# Grove_-_Sunlight_Sensor_v1_0.net
KiCad netlist of a schematic drawn in EAGLE
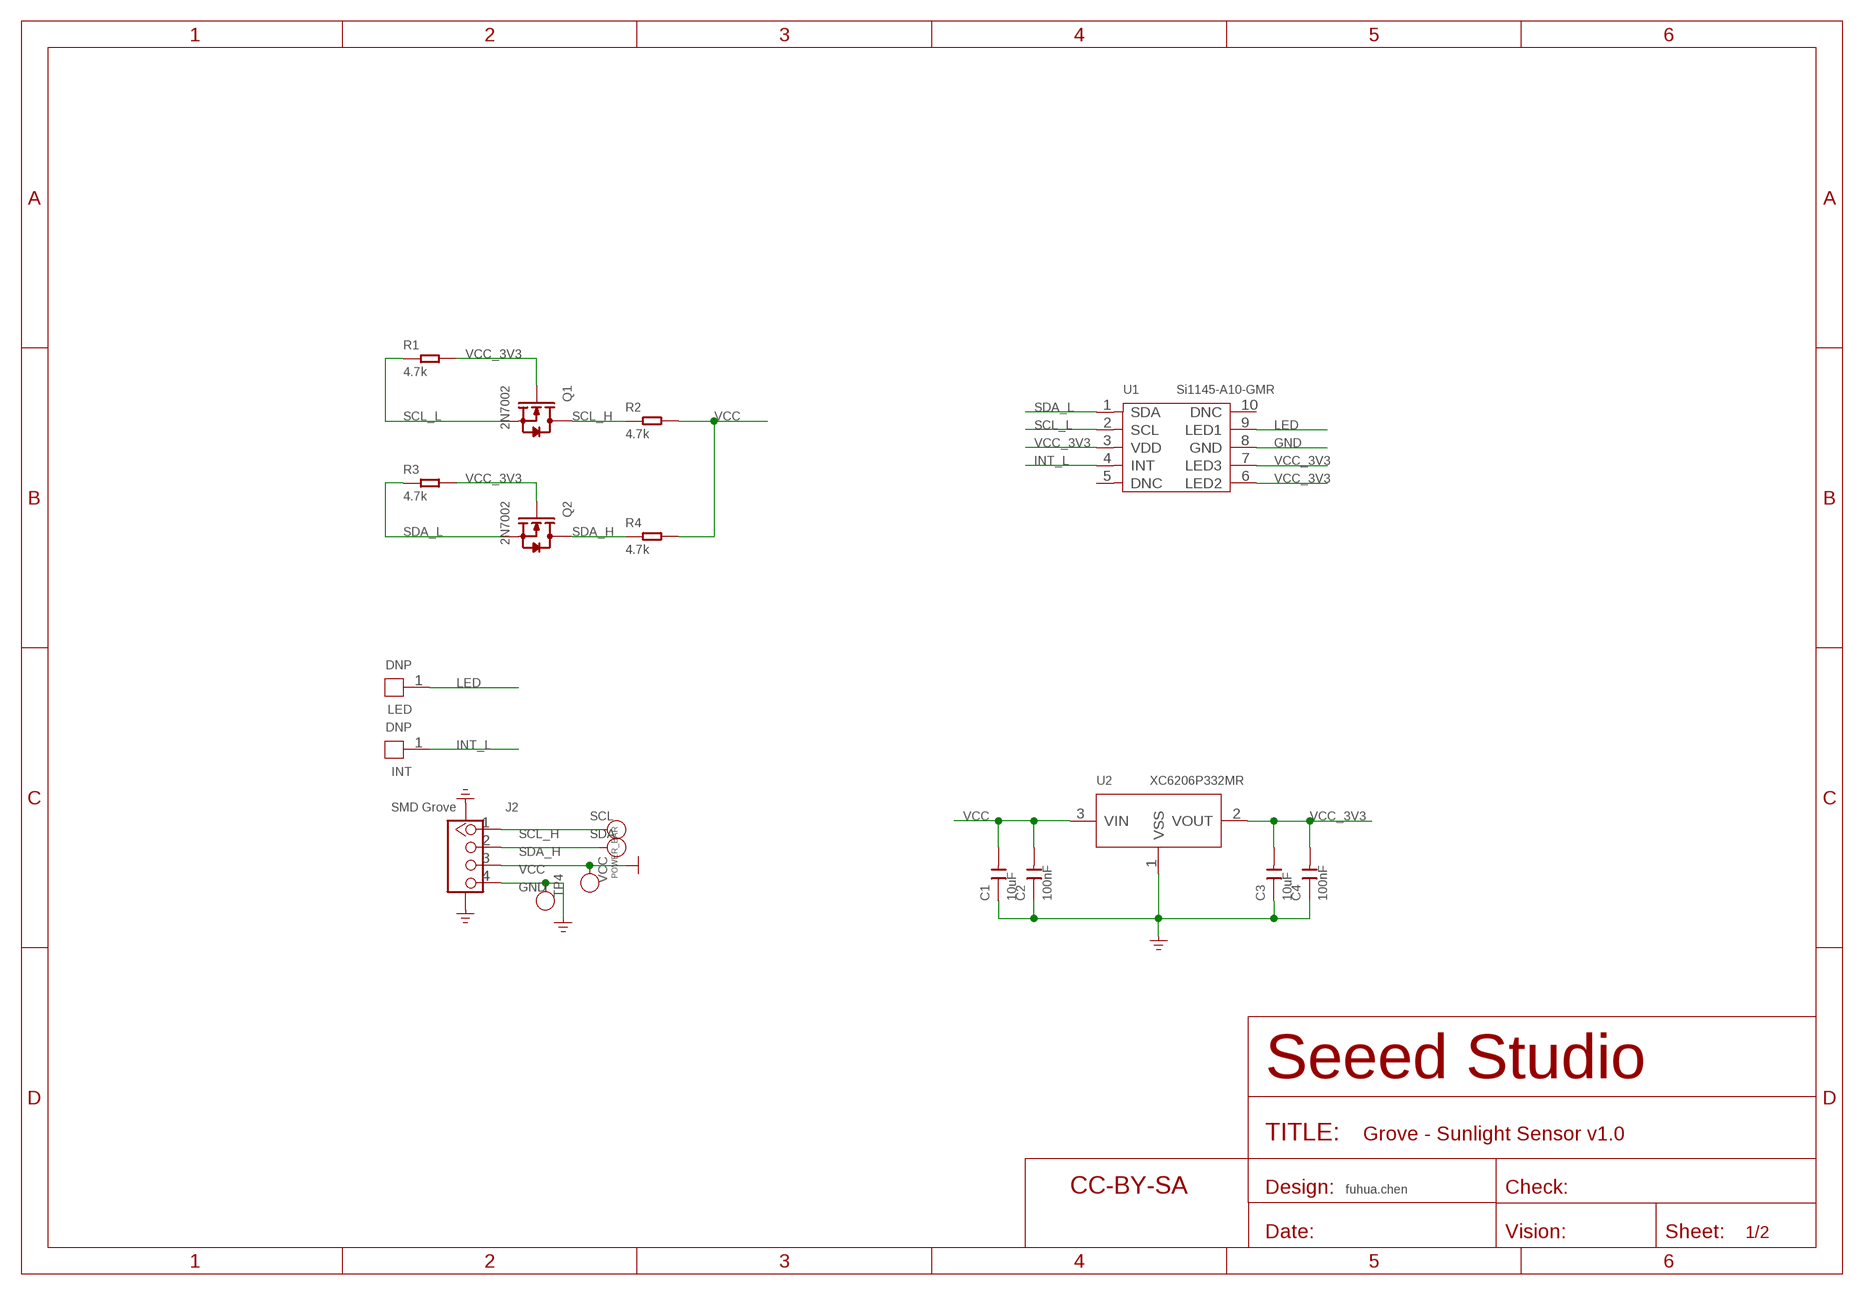
[diagram p0: schematic, sheet 1]
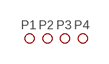
[diagram p1: schematic, sheet 2]

(export (version "E")
  (design (tool "Eeschema 10.0.6"))
  (components
    (comp (ref "C1")
      (value "10uF")
      (footprint "eagle-import:C0603")
      (libsource (lib "eagle-import") (part "CAP-0603"))
    )
    (comp (ref "C2")
      (value "100nF")
      (footprint "eagle-import:C0603")
      (libsource (lib "eagle-import") (part "CAP-0603"))
    )
    (comp (ref "C3")
      (value "10uF")
      (footprint "eagle-import:C0603")
      (libsource (lib "eagle-import") (part "CAP-0603"))
    )
    (comp (ref "C4")
      (value "100nF")
      (footprint "eagle-import:C0603")
      (libsource (lib "eagle-import") (part "CAP-0603"))
    )
    (comp (ref "FR")
      (value "SEEEDSTUDIO-OPEN-SCH-FRAME")
      (footprint "eagle-import:SEEEDSTUDIO-PCB-FRAME")
      (libsource (lib "eagle-import") (part "SEEEDSTUDIO-OPEN-SCH-FRAME"))
    )
    (comp (ref "INT")
      (value "DNP")
      (footprint "eagle-import:1P-80_40MIL")
      (libsource (lib "eagle-import") (part "HEADER-1P-40"))
    )
    (comp (ref "J2")
      (value "SMD Grove")
      (footprint "eagle-import:HW4-SMD-2.0")
      (libsource (lib "eagle-import") (part "GROVE-CONNECTOR-SMD'DD'"))
    )
    (comp (ref "LED")
      (value "DNP")
      (footprint "eagle-import:1P-80_40MIL")
      (libsource (lib "eagle-import") (part "HEADER-1P-40"))
    )
    (comp (ref "Q1")
      (value "2N7002")
      (footprint "eagle-import:SOT-23")
      (libsource (lib "eagle-import") (part "MOSFET-N'SOT23'"))
    )
    (comp (ref "Q2")
      (value "2N7002")
      (footprint "eagle-import:SOT-23")
      (libsource (lib "eagle-import") (part "MOSFET-N'SOT23'"))
    )
    (comp (ref "R1")
      (value "4.7k")
      (footprint "eagle-import:R0603")
      (libsource (lib "eagle-import") (part "RES-0603"))
    )
    (comp (ref "R2")
      (value "4.7k")
      (footprint "eagle-import:R0603")
      (libsource (lib "eagle-import") (part "RES-0603"))
    )
    (comp (ref "R3")
      (value "4.7k")
      (footprint "eagle-import:R0603")
      (libsource (lib "eagle-import") (part "RES-0603"))
    )
    (comp (ref "R4")
      (value "4.7k")
      (footprint "eagle-import:R0603")
      (libsource (lib "eagle-import") (part "RES-0603"))
    )
    (comp (ref "SCL")
      (value "TEST-POINT'4545'")
      (footprint "eagle-import:TP-D45MIL")
      (fields (field (name "PARTNO") "DNP"))
      (libsource (lib "eagle-import") (part "TEST-POINT'4545'"))
    )
    (comp (ref "SDA")
      (value "TEST-POINT'4545'")
      (footprint "eagle-import:TP-D45MIL")
      (fields (field (name "PARTNO") "DNP"))
      (libsource (lib "eagle-import") (part "TEST-POINT'4545'"))
    )
    (comp (ref "TP4")
      (value "TEST-POINT'4545'")
      (footprint "eagle-import:TP-D45MIL")
      (fields (field (name "PARTNO") "DNP"))
      (libsource (lib "eagle-import") (part "TEST-POINT'4545'"))
    )
    (comp (ref "U1")
      (value "Si1145-A10-GMR")
      (footprint "eagle-import:DFN10-0.5-2X2MM")
      (libsource (lib "eagle-import") (part "SENSOR-OPTICAL-SI1145/46/47"))
    )
    (comp (ref "U2")
      (value "XC6206P332MR")
      (footprint "eagle-import:SOT-23")
      (libsource (lib "eagle-import") (part "PMIC-XC6206PMR"))
    )
    (comp (ref "VCC")
      (value "TEST-POINT'4545'")
      (footprint "eagle-import:TP-D45MIL")
      (fields (field (name "PARTNO") "DNP"))
      (libsource (lib "eagle-import") (part "TEST-POINT'4545'"))
    )
    (comp (ref "P1")
      (value "PAD-MARK'ANNULAR'")
      (footprint "eagle-import:ROUND-MARK-1.0")
      (fields (field (name "PARTNO") "DNP"))
      (libsource (lib "eagle-import") (part "PAD-MARK'ANNULAR'"))
    )
    (comp (ref "P2")
      (value "PAD-MARK'ANNULAR'")
      (footprint "eagle-import:ROUND-MARK-1.0")
      (fields (field (name "PARTNO") "DNP"))
      (libsource (lib "eagle-import") (part "PAD-MARK'ANNULAR'"))
    )
    (comp (ref "P3")
      (value "PAD-MARK'ANNULAR'")
      (footprint "eagle-import:ROUND-MARK-1.0")
      (fields (field (name "PARTNO") "DNP"))
      (libsource (lib "eagle-import") (part "PAD-MARK'ANNULAR'"))
    )
    (comp (ref "P4")
      (value "PAD-MARK'ANNULAR'")
      (footprint "eagle-import:ROUND-MARK-1.0")
      (fields (field (name "PARTNO") "DNP"))
      (libsource (lib "eagle-import") (part "PAD-MARK'ANNULAR'"))
    )
  )
  (nets
    (net (code "1") (name "GND") (class "Default")
      (node (ref "C1") (pin "1") (pinfunction "1_1") (pintype "passive"))
      (node (ref "C2") (pin "1") (pinfunction "1_1") (pintype "passive"))
      (node (ref "C3") (pin "1") (pinfunction "1_1") (pintype "passive"))
      (node (ref "C4") (pin "1") (pinfunction "1_1") (pintype "passive"))
      (node (ref "J2") (pin "4") (pinfunction "4_4") (pintype "bidirectional"))
      (node (ref "J2") (pin "SS1") (pinfunction "SS1_SS1") (pintype "bidirectional"))
      (node (ref "J2") (pin "SS2") (pinfunction "SS2_SS2") (pintype "bidirectional"))
      (node (ref "TP4") (pin "T") (pinfunction "T_T") (pintype "bidirectional"))
      (node (ref "U1") (pin "8") (pinfunction "GND_8") (pintype "bidirectional"))
      (node (ref "U2") (pin "1") (pinfunction "VSS_1") (pintype "bidirectional"))
    )
    (net (code "2") (name "INT_L") (class "Default")
      (node (ref "INT") (pin "1") (pinfunction "1_1") (pintype "bidirectional"))
      (node (ref "U1") (pin "4") (pinfunction "INT_4") (pintype "bidirectional"))
    )
    (net (code "3") (name "LED") (class "Default")
      (node (ref "LED") (pin "1") (pinfunction "1_1") (pintype "bidirectional"))
      (node (ref "U1") (pin "9") (pinfunction "LED1_9") (pintype "bidirectional"))
    )
    (net (code "4") (name "SCL_H") (class "Default")
      (node (ref "J2") (pin "1") (pinfunction "1_1") (pintype "bidirectional"))
      (node (ref "Q1") (pin "3") (pinfunction "D_3") (pintype "passive"))
      (node (ref "R2") (pin "1") (pinfunction "1_1") (pintype "passive"))
      (node (ref "SCL") (pin "T") (pinfunction "T_T") (pintype "bidirectional"))
    )
    (net (code "5") (name "SCL_L") (class "Default")
      (node (ref "Q1") (pin "2") (pinfunction "S_2") (pintype "passive"))
      (node (ref "R1") (pin "1") (pinfunction "1_1") (pintype "passive"))
      (node (ref "U1") (pin "2") (pinfunction "SCL_2") (pintype "bidirectional"))
    )
    (net (code "6") (name "SDA_H") (class "Default")
      (node (ref "J2") (pin "2") (pinfunction "2_2") (pintype "bidirectional"))
      (node (ref "Q2") (pin "3") (pinfunction "D_3") (pintype "passive"))
      (node (ref "R4") (pin "1") (pinfunction "1_1") (pintype "passive"))
      (node (ref "SDA") (pin "T") (pinfunction "T_T") (pintype "bidirectional"))
    )
    (net (code "7") (name "SDA_L") (class "Default")
      (node (ref "Q2") (pin "2") (pinfunction "S_2") (pintype "passive"))
      (node (ref "R3") (pin "1") (pinfunction "1_1") (pintype "passive"))
      (node (ref "U1") (pin "1") (pinfunction "SDA_1") (pintype "bidirectional"))
    )
    (net (code "8") (name "VCC") (class "Default")
      (node (ref "C1") (pin "2") (pinfunction "2_2") (pintype "passive"))
      (node (ref "C2") (pin "2") (pinfunction "2_2") (pintype "passive"))
      (node (ref "J2") (pin "3") (pinfunction "3_3") (pintype "bidirectional"))
      (node (ref "R2") (pin "2") (pinfunction "2_2") (pintype "passive"))
      (node (ref "R4") (pin "2") (pinfunction "2_2") (pintype "passive"))
      (node (ref "U2") (pin "3") (pinfunction "VIN_3") (pintype "bidirectional"))
      (node (ref "VCC") (pin "T") (pinfunction "T_T") (pintype "bidirectional"))
    )
    (net (code "9") (name "VCC_3V3") (class "Default")
      (node (ref "C3") (pin "2") (pinfunction "2_2") (pintype "passive"))
      (node (ref "C4") (pin "2") (pinfunction "2_2") (pintype "passive"))
      (node (ref "Q1") (pin "1") (pinfunction "G_1") (pintype "passive"))
      (node (ref "Q2") (pin "1") (pinfunction "G_1") (pintype "passive"))
      (node (ref "R1") (pin "2") (pinfunction "2_2") (pintype "passive"))
      (node (ref "R3") (pin "2") (pinfunction "2_2") (pintype "passive"))
      (node (ref "U1") (pin "3") (pinfunction "VDD_3") (pintype "bidirectional"))
      (node (ref "U1") (pin "6") (pinfunction "LED2_6") (pintype "bidirectional"))
      (node (ref "U1") (pin "7") (pinfunction "LED3_7") (pintype "bidirectional"))
      (node (ref "U2") (pin "2") (pinfunction "VOUT_2") (pintype "bidirectional"))
    )
    (net (code "10") (name "unconnected-(U1-DNC-Pad5)") (class "Default")
      (node (ref "U1") (pin "5") (pinfunction "DNC_5") (pintype "bidirectional"))
    )
    (net (code "11") (name "unconnected-(U1-DNC-Pad10)") (class "Default")
      (node (ref "U1") (pin "10") (pinfunction "DNC_10") (pintype "bidirectional"))
    )
  )
)
